# BatteryMonitor.net
KiCad netlist of a schematic drawn in Altium Designer
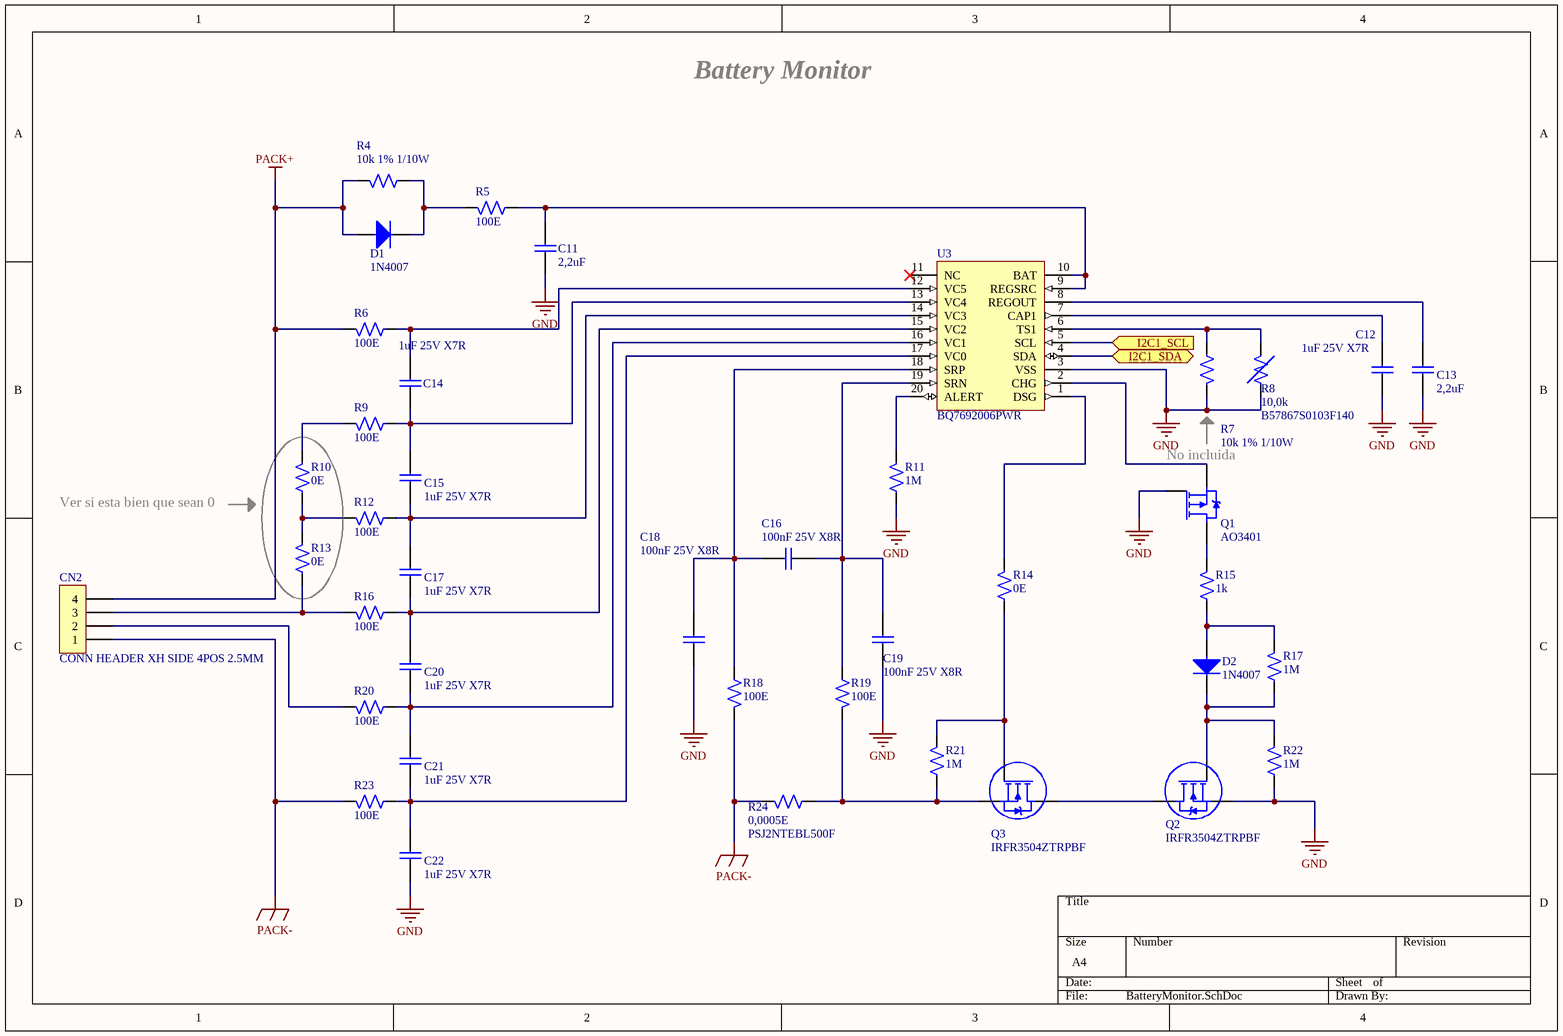
[diagram p0: BatteryMonitor.SchDoc]

(export (version "E")
  (design (tool "Eeschema 10.0.6"))
  (components
    (comp (ref "C11")
      (value "2,2uF 16V X7R")
      (footprint "C0603")
      (description "Capacitor de placas paralelas")
      (fields (field (name "VALOR") "2,2uF"))
      (libsource (lib "HW_Dron_V2") (part "Capacitor"))
    )
    (comp (ref "C12")
      (value "1uF 25V X7R")
      (footprint "C0603")
      (description "Capacitor de placas paralelas")
      (libsource (lib "HW_Dron_V2") (part "Capacitor"))
    )
    (comp (ref "C13")
      (value "2,2uF 16V X7R")
      (footprint "C0603")
      (description "Capacitor de placas paralelas")
      (fields (field (name "VALOR") "2,2uF"))
      (libsource (lib "HW_Dron_V2") (part "Capacitor"))
    )
    (comp (ref "C14")
      (value "1uF 25V X7R")
      (footprint "C0603")
      (description "Capacitor de placas paralelas")
      (libsource (lib "HW_Dron_V2") (part "Capacitor"))
    )
    (comp (ref "C15")
      (value "1uF 25V X7R")
      (footprint "C0603")
      (description "Capacitor de placas paralelas")
      (libsource (lib "HW_Dron_V2") (part "Capacitor"))
    )
    (comp (ref "C16")
      (value "100nF 25V X8R")
      (footprint "C0603")
      (description "Capacitor de placas paralelas")
      (libsource (lib "HW_Dron_V2") (part "Capacitor"))
    )
    (comp (ref "C17")
      (value "1uF 25V X7R")
      (footprint "C0603")
      (description "Capacitor de placas paralelas")
      (libsource (lib "HW_Dron_V2") (part "Capacitor"))
    )
    (comp (ref "C18")
      (value "100nF 25V X8R")
      (footprint "C0603")
      (description "Capacitor de placas paralelas")
      (libsource (lib "HW_Dron_V2") (part "Capacitor"))
    )
    (comp (ref "C19")
      (value "100nF 25V X8R")
      (footprint "C0603")
      (description "Capacitor de placas paralelas")
      (libsource (lib "HW_Dron_V2") (part "Capacitor"))
    )
    (comp (ref "C20")
      (value "1uF 25V X7R")
      (footprint "C0603")
      (description "Capacitor de placas paralelas")
      (libsource (lib "HW_Dron_V2") (part "Capacitor"))
    )
    (comp (ref "C21")
      (value "1uF 25V X7R")
      (footprint "C0603")
      (description "Capacitor de placas paralelas")
      (libsource (lib "HW_Dron_V2") (part "Capacitor"))
    )
    (comp (ref "C22")
      (value "1uF 25V X7R")
      (footprint "C0603")
      (description "Capacitor de placas paralelas")
      (libsource (lib "HW_Dron_V2") (part "Capacitor"))
    )
    (comp (ref "CN2")
      (value "CONN HEADER XH SIDE 4POS 2.5MM")
      (footprint "S4B-XH-A")
      (description "Header, 4-pin")
      (libsource (lib "HW_Dron_V2") (part "Header_4"))
    )
    (comp (ref "D1")
      (value "1N4007")
      (footprint "SMA (DO-214AC)")
      (description "Diodo")
      (libsource (lib "HW_Dron_V2") (part "Diode"))
    )
    (comp (ref "D2")
      (value "1N4007")
      (footprint "SMA (DO-214AC)")
      (description "Diodo")
      (libsource (lib "HW_Dron_V2") (part "Diode"))
    )
    (comp (ref "Q1")
      (value "AO3401")
      (footprint "SOT23")
      (description "P-Channel MOSFET")
      (libsource (lib "HW_Dron_V2") (part "MOSFET-P"))
    )
    (comp (ref "Q2")
      (value "IRFR3504ZTRPBF")
      (footprint "DPAK")
      (description "N-Channel Power MOSFET")
      (libsource (lib "HW_Dron_V2") (part "POWERMOSFET-N"))
    )
    (comp (ref "Q3")
      (value "IRFR3504ZTRPBF")
      (footprint "DPAK")
      (description "N-Channel Power MOSFET")
      (libsource (lib "HW_Dron_V2") (part "POWERMOSFET-N"))
    )
    (comp (ref "R4")
      (value "10k 1% 1/10W")
      (footprint "R0603")
      (description "Resistencia")
      (libsource (lib "HW_Dron_V2") (part "Resistor"))
    )
    (comp (ref "R5")
      (value "100E 5% 1/8W")
      (footprint "R0603")
      (description "Resistencia")
      (fields (field (name "VALOR") "100E"))
      (libsource (lib "HW_Dron_V2") (part "Resistor"))
    )
    (comp (ref "R6")
      (value "100E 5% 1/8W")
      (footprint "R0603")
      (description "Resistencia")
      (fields (field (name "VALOR") "100E"))
      (libsource (lib "HW_Dron_V2") (part "Resistor"))
    )
    (comp (ref "R7")
      (value "10k 1% 1/10W")
      (footprint "R0603")
      (description "Resistencia")
      (libsource (lib "HW_Dron_V2") (part "Resistor"))
    )
    (comp (ref "R8")
      (value "B57867S0103F140")
      (footprint "WF2S")
      (description "Termistor")
      (fields (field (name "VALOR") "10,0k"))
      (libsource (lib "HW_Dron_V2") (part "Termistor"))
    )
    (comp (ref "R9")
      (value "100E 5% 1/8W")
      (footprint "R0603")
      (description "Resistencia")
      (fields (field (name "VALOR") "100E"))
      (libsource (lib "HW_Dron_V2") (part "Resistor"))
    )
    (comp (ref "R10")
      (value "0E 5% 1/8W")
      (footprint "R0603")
      (description "Resistencia")
      (fields (field (name "VALOR") "0E"))
      (libsource (lib "HW_Dron_V2") (part "Resistor"))
    )
    (comp (ref "R11")
      (value "1M 5% 1/8W")
      (footprint "R0603")
      (description "Resistencia")
      (fields (field (name "VALOR") "1M"))
      (libsource (lib "HW_Dron_V2") (part "Resistor"))
    )
    (comp (ref "R12")
      (value "100E 5% 1/8W")
      (footprint "R0603")
      (description "Resistencia")
      (fields (field (name "VALOR") "100E"))
      (libsource (lib "HW_Dron_V2") (part "Resistor"))
    )
    (comp (ref "R13")
      (value "0E 5% 1/8W")
      (footprint "R0603")
      (description "Resistencia")
      (fields (field (name "VALOR") "0E"))
      (libsource (lib "HW_Dron_V2") (part "Resistor"))
    )
    (comp (ref "R14")
      (value "0E 5% 1/8W")
      (footprint "R0603")
      (description "Resistencia")
      (fields (field (name "VALOR") "0E"))
      (libsource (lib "HW_Dron_V2") (part "Resistor"))
    )
    (comp (ref "R15")
      (value "1k 5% 1/8W")
      (footprint "R0603")
      (description "Resistencia")
      (fields (field (name "VALOR") "1k"))
      (libsource (lib "HW_Dron_V2") (part "Resistor"))
    )
    (comp (ref "R16")
      (value "100E 5% 1/8W")
      (footprint "R0603")
      (description "Resistencia")
      (fields (field (name "VALOR") "100E"))
      (libsource (lib "HW_Dron_V2") (part "Resistor"))
    )
    (comp (ref "R17")
      (value "1M 5% 1/8W")
      (footprint "R0603")
      (description "Resistencia")
      (fields (field (name "VALOR") "1M"))
      (libsource (lib "HW_Dron_V2") (part "Resistor"))
    )
    (comp (ref "R18")
      (value "100E 5% 1/8W")
      (footprint "R0603")
      (description "Resistencia")
      (fields (field (name "VALOR") "100E"))
      (libsource (lib "HW_Dron_V2") (part "Resistor"))
    )
    (comp (ref "R19")
      (value "100E 5% 1/8W")
      (footprint "R0603")
      (description "Resistencia")
      (fields (field (name "VALOR") "100E"))
      (libsource (lib "HW_Dron_V2") (part "Resistor"))
    )
    (comp (ref "R20")
      (value "100E 5% 1/8W")
      (footprint "R0603")
      (description "Resistencia")
      (fields (field (name "VALOR") "100E"))
      (libsource (lib "HW_Dron_V2") (part "Resistor"))
    )
    (comp (ref "R21")
      (value "1M 5% 1/8W")
      (footprint "R0603")
      (description "Resistencia")
      (fields (field (name "VALOR") "1M"))
      (libsource (lib "HW_Dron_V2") (part "Resistor"))
    )
    (comp (ref "R22")
      (value "1M 5% 1/8W")
      (footprint "R0603")
      (description "Resistencia")
      (fields (field (name "VALOR") "1M"))
      (libsource (lib "HW_Dron_V2") (part "Resistor"))
    )
    (comp (ref "R23")
      (value "100E 5% 1/8W")
      (footprint "R0603")
      (description "Resistencia")
      (fields (field (name "VALOR") "100E"))
      (libsource (lib "HW_Dron_V2") (part "Resistor"))
    )
    (comp (ref "R24")
      (value "PSJ2NTEBL500F")
      (footprint "R0603")
      (description "Resistencia")
      (fields (field (name "VALOR") "0,0005E"))
      (libsource (lib "HW_Dron_V2") (part "Resistor"))
    )
    (comp (ref "U3")
      (value "BQ7692006PWR")
      (footprint "TSSOP20")
      (description "3-Series to 5-Series Cell Battery Monitor")
      (libsource (lib "HW_Dron_V2") (part "BQ76920"))
    )
  )
  (nets
    (net (code "1") (name "/I2C1_SCL") (class "Default")
      (node (ref "U3") (pin "5") (pinfunction "SCL_5") (pintype "input"))
    )
    (net (code "2") (name "/I2C1_SDA") (class "Default")
      (node (ref "U3") (pin "4") (pinfunction "SDA_4") (pintype "bidirectional"))
    )
    (net (code "3") (name "GND") (class "Default")
      (node (ref "C11") (pin "2") (pinfunction "2_2") (pintype "passive"))
      (node (ref "C12") (pin "2") (pinfunction "2_2") (pintype "passive"))
      (node (ref "C13") (pin "2") (pinfunction "2_2") (pintype "passive"))
      (node (ref "C18") (pin "2") (pinfunction "2_2") (pintype "passive"))
      (node (ref "C19") (pin "2") (pinfunction "2_2") (pintype "passive"))
      (node (ref "C22") (pin "2") (pinfunction "2_2") (pintype "passive"))
      (node (ref "Q1") (pin "1") (pinfunction "G_1") (pintype "passive"))
      (node (ref "Q2") (pin "3") (pinfunction "S_3") (pintype "passive"))
      (node (ref "R11") (pin "1") (pinfunction "1_1") (pintype "passive"))
      (node (ref "R22") (pin "1") (pinfunction "1_1") (pintype "passive"))
      (node (ref "R7") (pin "2") (pinfunction "2_2") (pintype "passive"))
      (node (ref "R8") (pin "1") (pinfunction "1_1") (pintype "passive"))
      (node (ref "U3") (pin "3") (pinfunction "VSS_3") (pintype "power_in"))
    )
    (net (code "4") (name "Net-(CN2-Pad2)") (class "Default")
      (node (ref "CN2") (pin "2") (pinfunction "2_2") (pintype "passive"))
      (node (ref "R20") (pin "2") (pinfunction "2_2") (pintype "passive"))
    )
    (net (code "5") (name "Net-(CN2-Pad3)") (class "Default")
      (node (ref "CN2") (pin "3") (pinfunction "3_3") (pintype "passive"))
      (node (ref "R13") (pin "1") (pinfunction "1_1") (pintype "passive"))
      (node (ref "R16") (pin "2") (pinfunction "2_2") (pintype "passive"))
    )
    (net (code "6") (name "Net-(D1-Pad2)") (class "Default")
      (node (ref "D1") (pin "2") (pinfunction "2_2") (pintype "passive"))
      (node (ref "R4") (pin "1") (pinfunction "1_1") (pintype "passive"))
      (node (ref "R5") (pin "2") (pinfunction "2_2") (pintype "passive"))
    )
    (net (code "7") (name "Net-(D2-Pad1)") (class "Default")
      (node (ref "D2") (pin "1") (pinfunction "1_1") (pintype "passive"))
      (node (ref "R15") (pin "1") (pinfunction "1_1") (pintype "passive"))
      (node (ref "R17") (pin "2") (pinfunction "2_2") (pintype "passive"))
    )
    (net (code "8") (name "Net-(Q1-D)") (class "Default")
      (node (ref "Q1") (pin "2") (pinfunction "D_2") (pintype "passive"))
      (node (ref "R15") (pin "2") (pinfunction "2_2") (pintype "passive"))
    )
    (net (code "9") (name "Net-(Q1-S)") (class "Default")
      (node (ref "Q1") (pin "3") (pinfunction "S_3") (pintype "passive"))
      (node (ref "U3") (pin "2") (pinfunction "CHG_2") (pintype "output"))
    )
    (net (code "10") (name "Net-(Q2-D)") (class "Default")
      (node (ref "Q2") (pin "2") (pinfunction "D_2") (pintype "passive"))
      (node (ref "Q3") (pin "2") (pinfunction "D_2") (pintype "passive"))
    )
    (net (code "11") (name "Net-(Q2-G)") (class "Default")
      (node (ref "D2") (pin "2") (pinfunction "2_2") (pintype "passive"))
      (node (ref "Q2") (pin "1") (pinfunction "G_1") (pintype "passive"))
      (node (ref "R17") (pin "1") (pinfunction "1_1") (pintype "passive"))
      (node (ref "R22") (pin "2") (pinfunction "2_2") (pintype "passive"))
    )
    (net (code "12") (name "Net-(Q3-G)") (class "Default")
      (node (ref "Q3") (pin "1") (pinfunction "G_1") (pintype "passive"))
      (node (ref "R14") (pin "1") (pinfunction "1_1") (pintype "passive"))
      (node (ref "R21") (pin "2") (pinfunction "2_2") (pintype "passive"))
    )
    (net (code "13") (name "Net-(Q3-S)") (class "Default")
      (node (ref "Q3") (pin "3") (pinfunction "S_3") (pintype "passive"))
      (node (ref "R19") (pin "2") (pinfunction "2_2") (pintype "passive"))
      (node (ref "R21") (pin "1") (pinfunction "1_1") (pintype "passive"))
      (node (ref "R24") (pin "1") (pinfunction "1_1") (pintype "passive"))
    )
    (net (code "14") (name "Net-(R10-Pad1)") (class "Default")
      (node (ref "R10") (pin "1") (pinfunction "1_1") (pintype "passive"))
      (node (ref "R12") (pin "2") (pinfunction "2_2") (pintype "passive"))
      (node (ref "R13") (pin "2") (pinfunction "2_2") (pintype "passive"))
    )
    (net (code "15") (name "Net-(R10-Pad2)") (class "Default")
      (node (ref "R10") (pin "2") (pinfunction "2_2") (pintype "passive"))
      (node (ref "R9") (pin "2") (pinfunction "2_2") (pintype "passive"))
    )
    (net (code "16") (name "Net-(U3-ALERT)") (class "Default")
      (node (ref "R11") (pin "2") (pinfunction "2_2") (pintype "passive"))
      (node (ref "U3") (pin "20") (pinfunction "ALERT_20") (pintype "bidirectional"))
    )
    (net (code "17") (name "Net-(U3-BAT)") (class "Default")
      (node (ref "C11") (pin "1") (pinfunction "1_1") (pintype "passive"))
      (node (ref "R5") (pin "1") (pinfunction "1_1") (pintype "passive"))
      (node (ref "U3") (pin "10") (pinfunction "BAT_10") (pintype "power_in"))
      (node (ref "U3") (pin "9") (pinfunction "REGSRC_9") (pintype "input"))
    )
    (net (code "18") (name "Net-(U3-CAP1)") (class "Default")
      (node (ref "C12") (pin "1") (pinfunction "1_1") (pintype "passive"))
      (node (ref "U3") (pin "7") (pinfunction "CAP1_7") (pintype "output"))
    )
    (net (code "19") (name "Net-(U3-DSG)") (class "Default")
      (node (ref "R14") (pin "2") (pinfunction "2_2") (pintype "passive"))
      (node (ref "U3") (pin "1") (pinfunction "DSG_1") (pintype "output"))
    )
    (net (code "20") (name "Net-(U3-REGOUT)") (class "Default")
      (node (ref "C13") (pin "1") (pinfunction "1_1") (pintype "passive"))
      (node (ref "U3") (pin "8") (pinfunction "REGOUT_8") (pintype "power_in"))
    )
    (net (code "21") (name "Net-(U3-SRN)") (class "Default")
      (node (ref "C16") (pin "2") (pinfunction "2_2") (pintype "passive"))
      (node (ref "C19") (pin "1") (pinfunction "1_1") (pintype "passive"))
      (node (ref "R19") (pin "1") (pinfunction "1_1") (pintype "passive"))
      (node (ref "U3") (pin "19") (pinfunction "SRN_19") (pintype "input"))
    )
    (net (code "22") (name "Net-(U3-SRP)") (class "Default")
      (node (ref "C16") (pin "1") (pinfunction "1_1") (pintype "passive"))
      (node (ref "C18") (pin "1") (pinfunction "1_1") (pintype "passive"))
      (node (ref "R18") (pin "1") (pinfunction "1_1") (pintype "passive"))
      (node (ref "U3") (pin "18") (pinfunction "SRP_18") (pintype "input"))
    )
    (net (code "23") (name "Net-(U3-TS1)") (class "Default")
      (node (ref "R7") (pin "1") (pinfunction "1_1") (pintype "passive"))
      (node (ref "R8") (pin "2") (pinfunction "2_2") (pintype "passive"))
      (node (ref "U3") (pin "6") (pinfunction "TS1_6") (pintype "input"))
    )
    (net (code "24") (name "Net-(U3-VC0)") (class "Default")
      (node (ref "C21") (pin "2") (pinfunction "2_2") (pintype "passive"))
      (node (ref "C22") (pin "1") (pinfunction "1_1") (pintype "passive"))
      (node (ref "R23") (pin "1") (pinfunction "1_1") (pintype "passive"))
      (node (ref "U3") (pin "17") (pinfunction "VC0_17") (pintype "input"))
    )
    (net (code "25") (name "Net-(U3-VC1)") (class "Default")
      (node (ref "C20") (pin "2") (pinfunction "2_2") (pintype "passive"))
      (node (ref "C21") (pin "1") (pinfunction "1_1") (pintype "passive"))
      (node (ref "R20") (pin "1") (pinfunction "1_1") (pintype "passive"))
      (node (ref "U3") (pin "16") (pinfunction "VC1_16") (pintype "input"))
    )
    (net (code "26") (name "Net-(U3-VC2)") (class "Default")
      (node (ref "C17") (pin "2") (pinfunction "2_2") (pintype "passive"))
      (node (ref "C20") (pin "1") (pinfunction "1_1") (pintype "passive"))
      (node (ref "R16") (pin "1") (pinfunction "1_1") (pintype "passive"))
      (node (ref "U3") (pin "15") (pinfunction "VC2_15") (pintype "input"))
    )
    (net (code "27") (name "Net-(U3-VC3)") (class "Default")
      (node (ref "C15") (pin "2") (pinfunction "2_2") (pintype "passive"))
      (node (ref "C17") (pin "1") (pinfunction "1_1") (pintype "passive"))
      (node (ref "R12") (pin "1") (pinfunction "1_1") (pintype "passive"))
      (node (ref "U3") (pin "14") (pinfunction "VC3_14") (pintype "input"))
    )
    (net (code "28") (name "Net-(U3-VC4)") (class "Default")
      (node (ref "C14") (pin "2") (pinfunction "2_2") (pintype "passive"))
      (node (ref "C15") (pin "1") (pinfunction "1_1") (pintype "passive"))
      (node (ref "R9") (pin "1") (pinfunction "1_1") (pintype "passive"))
      (node (ref "U3") (pin "13") (pinfunction "VC4_13") (pintype "input"))
    )
    (net (code "29") (name "Net-(U3-VC5)") (class "Default")
      (node (ref "C14") (pin "1") (pinfunction "1_1") (pintype "passive"))
      (node (ref "R6") (pin "1") (pinfunction "1_1") (pintype "passive"))
      (node (ref "U3") (pin "12") (pinfunction "VC5_12") (pintype "input"))
    )
    (net (code "30") (name "PACK+") (class "Default")
      (node (ref "CN2") (pin "4") (pinfunction "4_4") (pintype "passive"))
      (node (ref "D1") (pin "1") (pinfunction "1_1") (pintype "passive"))
      (node (ref "R4") (pin "2") (pinfunction "2_2") (pintype "passive"))
      (node (ref "R6") (pin "2") (pinfunction "2_2") (pintype "passive"))
    )
    (net (code "31") (name "PACK-") (class "Default")
      (node (ref "CN2") (pin "1") (pinfunction "1_1") (pintype "passive"))
      (node (ref "R18") (pin "2") (pinfunction "2_2") (pintype "passive"))
      (node (ref "R23") (pin "2") (pinfunction "2_2") (pintype "passive"))
      (node (ref "R24") (pin "2") (pinfunction "2_2") (pintype "passive"))
    )
    (net (code "32") (name "unconnected-(U3-NC-Pad11)") (class "Default")
      (node (ref "U3") (pin "11") (pinfunction "NC_11") (pintype "tri_state+no_connect"))
    )
  )
)
